# NE555_GEN_switchLEDv1.net
KiCad netlist of a schematic drawn in EAGLE
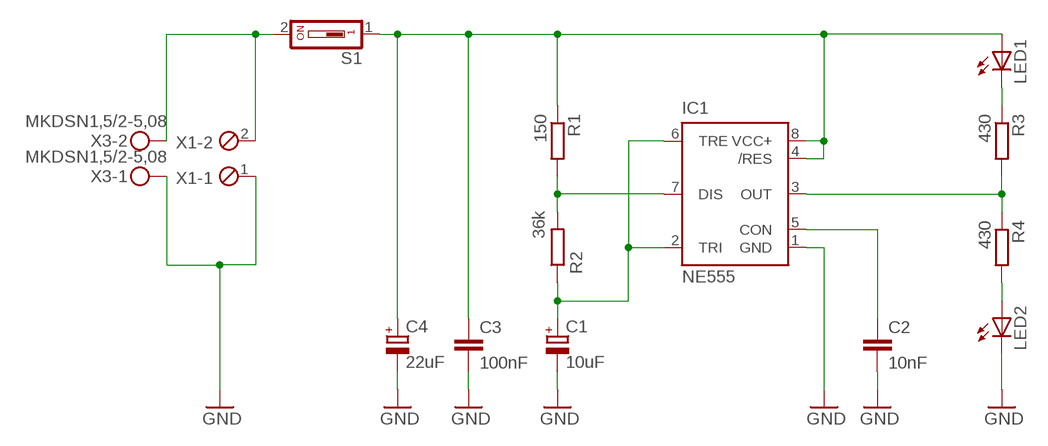
[diagram p0: schematic, sheet 1]

(export (version "E")
  (design (tool "Eeschema 10.0.6"))
  (components
    (comp (ref "C1")
      (value "10uF")
      (footprint "eagle-import:E2,5-5")
      (libsource (lib "eagle-import") (part "CPOL-EUE2.5-5"))
    )
    (comp (ref "C2")
      (value "10nF")
      (footprint "eagle-import:C050-024X044")
      (libsource (lib "eagle-import") (part "C-EU050-024X044"))
    )
    (comp (ref "C3")
      (value "100nF")
      (footprint "eagle-import:C025-024X044")
      (libsource (lib "eagle-import") (part "C-EU025-024X044"))
    )
    (comp (ref "C4")
      (value "22uF")
      (footprint "eagle-import:E2,5-7")
      (libsource (lib "eagle-import") (part "CPOL-EUE2.5-7"))
    )
    (comp (ref "IC1")
      (value "NE555")
      (footprint "eagle-import:DIL-08")
      (fields (field (name "MF") "Arrow Electronics") (field (name "MPN") "NE555N"))
      (libsource (lib "eagle-import") (part "NE555"))
    )
    (comp (ref "LED1")
      (value "LED5MM")
      (footprint "eagle-import:LED5MM")
      (libsource (lib "eagle-import") (part "LED5MM"))
    )
    (comp (ref "LED2")
      (value "LED5MM")
      (footprint "eagle-import:LED5MM")
      (libsource (lib "eagle-import") (part "LED5MM"))
    )
    (comp (ref "R1")
      (value "150")
      (footprint "eagle-import:0207_7")
      (libsource (lib "eagle-import") (part "R-EU_0207/7"))
    )
    (comp (ref "R2")
      (value "36k")
      (footprint "eagle-import:0207_7")
      (libsource (lib "eagle-import") (part "R-EU_0207/7"))
    )
    (comp (ref "R3")
      (value "430")
      (footprint "eagle-import:0207_7")
      (libsource (lib "eagle-import") (part "R-EU_0207/7"))
    )
    (comp (ref "R4")
      (value "430")
      (footprint "eagle-import:0207_7")
      (libsource (lib "eagle-import") (part "R-EU_0207/7"))
    )
    (comp (ref "S1")
      (value "DS01")
      (footprint "eagle-import:DS-01")
      (libsource (lib "eagle-import") (part "DS01"))
    )
    (comp (ref "X1")
      (value "MPT2")
      (footprint "eagle-import:2POL254")
      (libsource (lib "eagle-import") (part "MPT2"))
    )
    (comp (ref "X3")
      (value "MKDSN1,5/2-5,08")
      (footprint "eagle-import:MKDSN1,5_2-5,08")
      (libsource (lib "eagle-import") (part "MKDSN1,5/2-5,08"))
    )
  )
  (nets
    (net (code "1") (name "GND") (class "Default")
      (node (ref "C1") (pin "-") (pinfunction "-_-") (pintype "passive"))
      (node (ref "C2") (pin "2") (pinfunction "2_2") (pintype "passive"))
      (node (ref "C3") (pin "2") (pinfunction "2_2") (pintype "passive"))
      (node (ref "C4") (pin "-") (pinfunction "-_-") (pintype "passive"))
      (node (ref "IC1") (pin "1") (pinfunction "GND_1") (pintype "power_in"))
      (node (ref "LED2") (pin "K") (pinfunction "C_K") (pintype "passive"))
      (node (ref "X1") (pin "1") (pinfunction "1_1") (pintype "passive"))
      (node (ref "X3") (pin "1") (pinfunction "KL_1") (pintype "passive"))
    )
    (net (code "2") (name "Net-(IC1-CON)") (class "Default")
      (node (ref "C2") (pin "1") (pinfunction "1_1") (pintype "passive"))
      (node (ref "IC1") (pin "5") (pinfunction "CON_5") (pintype "input"))
    )
    (net (code "3") (name "Net-(IC1-DIS)") (class "Default")
      (node (ref "IC1") (pin "7") (pinfunction "DIS_7") (pintype "input"))
      (node (ref "R1") (pin "2") (pinfunction "2_2") (pintype "passive"))
      (node (ref "R2") (pin "2") (pinfunction "2_2") (pintype "passive"))
    )
    (net (code "4") (name "Net-(IC1-OUT)") (class "Default")
      (node (ref "IC1") (pin "3") (pinfunction "OUT_3") (pintype "output"))
      (node (ref "R3") (pin "2") (pinfunction "2_2") (pintype "passive"))
      (node (ref "R4") (pin "1") (pinfunction "1_1") (pintype "passive"))
    )
    (net (code "5") (name "Net-(IC1-TRE)") (class "Default")
      (node (ref "C1") (pin "+") (pinfunction "+_+") (pintype "passive"))
      (node (ref "IC1") (pin "2") (pinfunction "TRI_2") (pintype "input"))
      (node (ref "IC1") (pin "6") (pinfunction "TRE_6") (pintype "input"))
      (node (ref "R2") (pin "1") (pinfunction "1_1") (pintype "passive"))
    )
    (net (code "6") (name "Net-(IC1-VCC+)") (class "Default")
      (node (ref "C3") (pin "1") (pinfunction "1_1") (pintype "passive"))
      (node (ref "C4") (pin "+") (pinfunction "+_+") (pintype "passive"))
      (node (ref "IC1") (pin "4") (pinfunction "/RES_4") (pintype "input"))
      (node (ref "IC1") (pin "8") (pinfunction "VCC+_8") (pintype "power_in"))
      (node (ref "LED1") (pin "A") (pinfunction "A_A") (pintype "passive"))
      (node (ref "R1") (pin "1") (pinfunction "1_1") (pintype "passive"))
      (node (ref "S1") (pin "1") (pinfunction "1_1") (pintype "passive"))
    )
    (net (code "7") (name "Net-(LED1-C)") (class "Default")
      (node (ref "LED1") (pin "K") (pinfunction "C_K") (pintype "passive"))
      (node (ref "R3") (pin "1") (pinfunction "1_1") (pintype "passive"))
    )
    (net (code "8") (name "Net-(LED2-PadA)") (class "Default")
      (node (ref "LED2") (pin "A") (pinfunction "A_A") (pintype "passive"))
      (node (ref "R4") (pin "2") (pinfunction "2_2") (pintype "passive"))
    )
    (net (code "9") (name "Net-(X1B-1)") (class "Default")
      (node (ref "S1") (pin "2") (pinfunction "2_2") (pintype "passive"))
      (node (ref "X1") (pin "2") (pinfunction "1_2") (pintype "passive"))
      (node (ref "X3") (pin "2") (pinfunction "KL_2") (pintype "passive"))
    )
  )
)
